# usb_io_v3_sch.net
KiCad netlist of a schematic drawn in Altium Designer
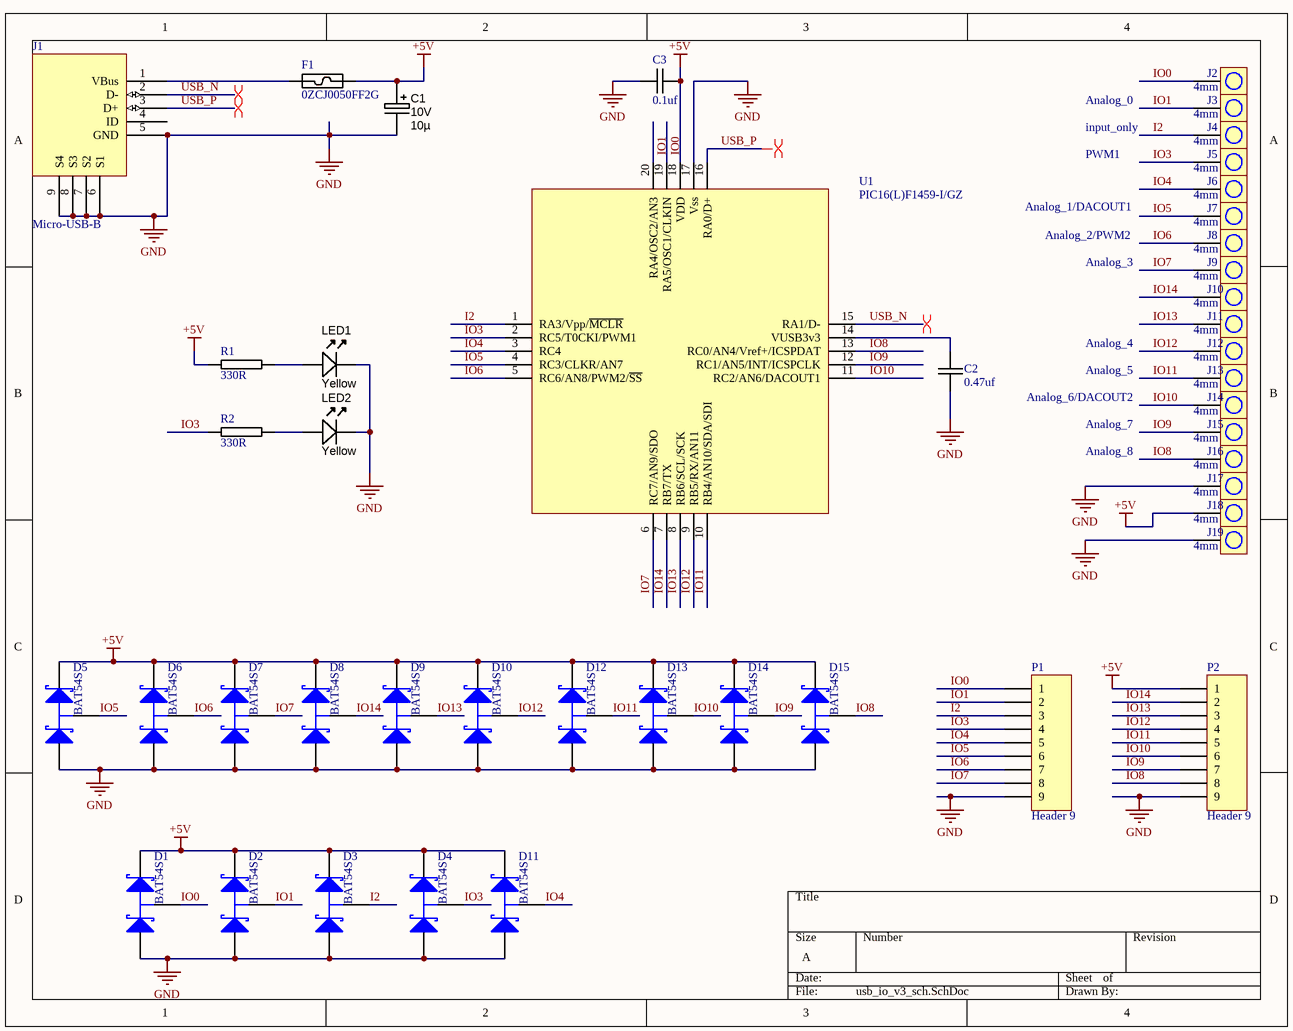
[diagram p0: usb_io_v3_sch.SchDoc]

(export (version "E")
  (design (tool "Eeschema 10.0.6"))
  (components
    (comp (ref "C1")
      (value "10µ")
      (footprint "CAPMP3528X210N")
      (description "Capacitor SMD Tantalum 47uF 20% 6.3V 1210")
      (fields (field (name "TOLERANCE") "±20%") (field (name "RATINGS") "10V"))
      (libsource (lib "PBL - Capacitors") (part "CAPT_47u_1210_6V3"))
    )
    (comp (ref "C2")
      (value "0.47uf")
      (footprint "0603C-GENERIC")
      (description "CAPACITOR 0603 CERAMIC")
      (fields
        (field (name "MANUFACTURER") "Murata Electronics North America")
        (field (name "MANUFACTURER PART NUMBER") "GRM188R60J106ME47D")
      )
      (libsource (lib "Generic") (part "0603C-10UF-6V3-X5R-MUR"))
    )
    (comp (ref "C3")
      (value "0.1uf")
      (footprint "0603C-GENERIC")
      (description "CAPACITOR 0603 CERAMIC")
      (fields
        (field (name "MANUFACTURER") "Murata Electronics North America")
        (field (name "MANUFACTURER PART NUMBER") "GRM188R60J106ME47D")
      )
      (libsource (lib "Generic") (part "0603C-10UF-6V3-X5R-MUR"))
    )
    (comp (ref "D1")
      (value "BAT54S")
      (footprint "SOT23_N")
      (description "Schottky Barrier Double Diode")
      (fields (field (name "PUBLISHER") "Altium Limited"))
      (libsource (lib "Philips Discrete Diode - Schottky") (part "BAT54S"))
    )
    (comp (ref "D2")
      (value "BAT54S")
      (footprint "SOT23_N")
      (description "Schottky Barrier Double Diode")
      (fields (field (name "PUBLISHER") "Altium Limited"))
      (libsource (lib "Philips Discrete Diode - Schottky") (part "BAT54S"))
    )
    (comp (ref "D3")
      (value "BAT54S")
      (footprint "SOT23_N")
      (description "Schottky Barrier Double Diode")
      (fields (field (name "PUBLISHER") "Altium Limited"))
      (libsource (lib "Philips Discrete Diode - Schottky") (part "BAT54S"))
    )
    (comp (ref "D4")
      (value "BAT54S")
      (footprint "SOT23_N")
      (description "Schottky Barrier Double Diode")
      (fields (field (name "PUBLISHER") "Altium Limited"))
      (libsource (lib "Philips Discrete Diode - Schottky") (part "BAT54S"))
    )
    (comp (ref "D5")
      (value "BAT54S")
      (footprint "SOT23_N")
      (description "Schottky Barrier Double Diode")
      (fields (field (name "PUBLISHER") "Altium Limited"))
      (libsource (lib "Philips Discrete Diode - Schottky") (part "BAT54S"))
    )
    (comp (ref "D6")
      (value "BAT54S")
      (footprint "SOT23_N")
      (description "Schottky Barrier Double Diode")
      (fields (field (name "PUBLISHER") "Altium Limited"))
      (libsource (lib "Philips Discrete Diode - Schottky") (part "BAT54S"))
    )
    (comp (ref "D7")
      (value "BAT54S")
      (footprint "SOT23_N")
      (description "Schottky Barrier Double Diode")
      (fields (field (name "PUBLISHER") "Altium Limited"))
      (libsource (lib "Philips Discrete Diode - Schottky") (part "BAT54S"))
    )
    (comp (ref "D8")
      (value "BAT54S")
      (footprint "SOT23_N")
      (description "Schottky Barrier Double Diode")
      (fields (field (name "PUBLISHER") "Altium Limited"))
      (libsource (lib "Philips Discrete Diode - Schottky") (part "BAT54S"))
    )
    (comp (ref "D9")
      (value "BAT54S")
      (footprint "SOT23_N")
      (description "Schottky Barrier Double Diode")
      (fields (field (name "PUBLISHER") "Altium Limited"))
      (libsource (lib "Philips Discrete Diode - Schottky") (part "BAT54S"))
    )
    (comp (ref "D10")
      (value "BAT54S")
      (footprint "SOT23_N")
      (description "Schottky Barrier Double Diode")
      (fields (field (name "PUBLISHER") "Altium Limited"))
      (libsource (lib "Philips Discrete Diode - Schottky") (part "BAT54S"))
    )
    (comp (ref "D11")
      (value "BAT54S")
      (footprint "SOT23_N")
      (description "Schottky Barrier Double Diode")
      (fields (field (name "PUBLISHER") "Altium Limited"))
      (libsource (lib "Philips Discrete Diode - Schottky") (part "BAT54S"))
    )
    (comp (ref "D12")
      (value "BAT54S")
      (footprint "SOT23_N")
      (description "Schottky Barrier Double Diode")
      (fields (field (name "PUBLISHER") "Altium Limited"))
      (libsource (lib "Philips Discrete Diode - Schottky") (part "BAT54S"))
    )
    (comp (ref "D13")
      (value "BAT54S")
      (footprint "SOT23_N")
      (description "Schottky Barrier Double Diode")
      (fields (field (name "PUBLISHER") "Altium Limited"))
      (libsource (lib "Philips Discrete Diode - Schottky") (part "BAT54S"))
    )
    (comp (ref "D14")
      (value "BAT54S")
      (footprint "SOT23_N")
      (description "Schottky Barrier Double Diode")
      (fields (field (name "PUBLISHER") "Altium Limited"))
      (libsource (lib "Philips Discrete Diode - Schottky") (part "BAT54S"))
    )
    (comp (ref "D15")
      (value "BAT54S")
      (footprint "SOT23_N")
      (description "Schottky Barrier Double Diode")
      (fields (field (name "PUBLISHER") "Altium Limited"))
      (libsource (lib "Philips Discrete Diode - Schottky") (part "BAT54S"))
    )
    (comp (ref "F1")
      (value "0ZCJ0050FF2G")
      (footprint "RESC3216N")
      (description "GENERIC FUSE")
      (libsource (lib "Generic") (part "FUSE-GENERIC"))
    )
    (comp (ref "J1")
      (value "Micro-USB-B")
      (footprint "10118193-0001lfc")
      (libsource (lib "USB-MICROB-HW-MC-5F") (part "Micro-USB-B"))
    )
    (comp (ref "J2")
      (value "4mm")
      (footprint "header_4mm_drill")
      (libsource (lib "headers") (part "Banana_4mm"))
    )
    (comp (ref "J3")
      (value "4mm")
      (footprint "header_4mm_drill")
      (libsource (lib "headers") (part "Banana_4mm"))
    )
    (comp (ref "J4")
      (value "4mm")
      (footprint "header_4mm_drill")
      (libsource (lib "headers") (part "Banana_4mm"))
    )
    (comp (ref "J5")
      (value "4mm")
      (footprint "header_4mm_drill")
      (libsource (lib "headers") (part "Banana_4mm"))
    )
    (comp (ref "J6")
      (value "4mm")
      (footprint "header_4mm_drill")
      (libsource (lib "headers") (part "Banana_4mm"))
    )
    (comp (ref "J7")
      (value "4mm")
      (footprint "header_4mm_drill")
      (libsource (lib "headers") (part "Banana_4mm"))
    )
    (comp (ref "J8")
      (value "4mm")
      (footprint "header_4mm_drill")
      (libsource (lib "headers") (part "Banana_4mm"))
    )
    (comp (ref "J9")
      (value "4mm")
      (footprint "header_4mm_drill")
      (libsource (lib "headers") (part "Banana_4mm"))
    )
    (comp (ref "J10")
      (value "4mm")
      (footprint "header_4mm_drill")
      (libsource (lib "headers") (part "Banana_4mm"))
    )
    (comp (ref "J11")
      (value "4mm")
      (footprint "header_4mm_drill")
      (libsource (lib "headers") (part "Banana_4mm"))
    )
    (comp (ref "J12")
      (value "4mm")
      (footprint "header_4mm_drill")
      (libsource (lib "headers") (part "Banana_4mm"))
    )
    (comp (ref "J13")
      (value "4mm")
      (footprint "header_4mm_drill")
      (libsource (lib "headers") (part "Banana_4mm"))
    )
    (comp (ref "J14")
      (value "4mm")
      (footprint "header_4mm_drill")
      (libsource (lib "headers") (part "Banana_4mm"))
    )
    (comp (ref "J15")
      (value "4mm")
      (footprint "header_4mm_drill")
      (libsource (lib "headers") (part "Banana_4mm"))
    )
    (comp (ref "J16")
      (value "4mm")
      (footprint "header_4mm_drill")
      (libsource (lib "headers") (part "Banana_4mm"))
    )
    (comp (ref "J17")
      (value "4mm")
      (footprint "header_4mm_drill")
      (libsource (lib "headers") (part "Banana_4mm"))
    )
    (comp (ref "J18")
      (value "4mm")
      (footprint "header_4mm_drill")
      (libsource (lib "headers") (part "Banana_4mm"))
    )
    (comp (ref "J19")
      (value "4mm")
      (footprint "header_4mm_drill")
      (libsource (lib "headers") (part "Banana_4mm"))
    )
    (comp (ref "LED1")
      (value "Yellow")
      (footprint "LED-0603-YELLOW")
      (description "LED 0603 SMD Yellow 590nm 150mcd 20mA")
      (libsource (lib "PBL - Light Sources") (part "LED_SMD_Yellow_0603_150mcd"))
    )
    (comp (ref "LED2")
      (value "Yellow")
      (footprint "LED-0603-YELLOW")
      (description "LED 0603 SMD Yellow 590nm 150mcd 20mA")
      (libsource (lib "PBL - Light Sources") (part "LED_SMD_Yellow_0603_150mcd"))
    )
    (comp (ref "P1")
      (value "Header 9")
      (footprint "HDR1X9")
      (description "Header, 9-Pin")
      (fields (field (name "PUBLISHER") "Altium Limited"))
      (libsource (lib "Miscellaneous Connectors") (part "Header 9"))
    )
    (comp (ref "P2")
      (value "Header 9")
      (footprint "HDR1X9")
      (description "Header, 9-Pin")
      (fields (field (name "PUBLISHER") "Altium Limited"))
      (libsource (lib "Miscellaneous Connectors") (part "Header 9"))
    )
    (comp (ref "R1")
      (value "330R")
      (footprint "0603R-2K2")
      (description "GENERIC RESISTOR 0603")
      (fields
        (field (name "MANUFACTURER PART NUMBER") "RMC 1/16 2.2K 1% R")
        (field (name "MANUFACTURER") "Stackpole Electronics Inc")
      )
      (libsource (lib "Generic") (part "0603R-2K2"))
    )
    (comp (ref "R2")
      (value "330R")
      (footprint "0603R-2K2")
      (description "GENERIC RESISTOR 0603")
      (fields
        (field (name "MANUFACTURER PART NUMBER") "RMC 1/16 2.2K 1% R")
        (field (name "MANUFACTURER") "Stackpole Electronics Inc")
      )
      (libsource (lib "Generic") (part "0603R-2K2"))
    )
    (comp (ref "U1")
      (value "PIC16(L)F1459-I/GZ")
      (footprint "UQFN20_4x4")
      (libsource (lib "microchip_my") (part "PIC16(L)F1459-I/GZ"))
    )
  )
  (nets
    (net (code "1") (name "+5V") (class "Default")
      (node (ref "C1") (pin "1") (pintype "passive"))
      (node (ref "C3") (pin "2") (pintype "passive"))
      (node (ref "D1") (pin "2") (pinfunction "K_2") (pintype "passive"))
      (node (ref "D10") (pin "2") (pinfunction "K_2") (pintype "passive"))
      (node (ref "D11") (pin "2") (pinfunction "K_2") (pintype "passive"))
      (node (ref "D12") (pin "2") (pinfunction "K_2") (pintype "passive"))
      (node (ref "D13") (pin "2") (pinfunction "K_2") (pintype "passive"))
      (node (ref "D14") (pin "2") (pinfunction "K_2") (pintype "passive"))
      (node (ref "D15") (pin "2") (pinfunction "K_2") (pintype "passive"))
      (node (ref "D2") (pin "2") (pinfunction "K_2") (pintype "passive"))
      (node (ref "D3") (pin "2") (pinfunction "K_2") (pintype "passive"))
      (node (ref "D4") (pin "2") (pinfunction "K_2") (pintype "passive"))
      (node (ref "D5") (pin "2") (pinfunction "K_2") (pintype "passive"))
      (node (ref "D6") (pin "2") (pinfunction "K_2") (pintype "passive"))
      (node (ref "D7") (pin "2") (pinfunction "K_2") (pintype "passive"))
      (node (ref "D8") (pin "2") (pinfunction "K_2") (pintype "passive"))
      (node (ref "D9") (pin "2") (pinfunction "K_2") (pintype "passive"))
      (node (ref "F1") (pin "2") (pintype "passive"))
      (node (ref "J18") (pin "1") (pinfunction "1_1") (pintype "passive"))
      (node (ref "P2") (pin "1") (pinfunction "1_1") (pintype "passive"))
      (node (ref "R1") (pin "2") (pintype "passive"))
      (node (ref "U1") (pin "18") (pinfunction "VDD_18") (pintype "power_in"))
    )
    (net (code "2") (name "/I2") (class "Default")
      (node (ref "D3") (pin "3") (pinfunction "C_3") (pintype "passive"))
      (node (ref "J4") (pin "1") (pinfunction "1_1") (pintype "passive"))
      (node (ref "P1") (pin "3") (pinfunction "3_3") (pintype "passive"))
      (node (ref "U1") (pin "1") (pinfunction "RA3/Vpp/~{MCLR}_1") (pintype "passive"))
    )
    (net (code "3") (name "/IO0") (class "Default")
      (node (ref "D1") (pin "3") (pinfunction "C_3") (pintype "passive"))
      (node (ref "J2") (pin "1") (pinfunction "1_1") (pintype "passive"))
      (node (ref "P1") (pin "1") (pinfunction "1_1") (pintype "passive"))
      (node (ref "U1") (pin "19") (pinfunction "RA5/OSC1/CLKIN_19") (pintype "passive"))
    )
    (net (code "4") (name "/IO1") (class "Default")
      (node (ref "D2") (pin "3") (pinfunction "C_3") (pintype "passive"))
      (node (ref "J3") (pin "1") (pinfunction "1_1") (pintype "passive"))
      (node (ref "P1") (pin "2") (pinfunction "2_2") (pintype "passive"))
      (node (ref "U1") (pin "20") (pinfunction "RA4/OSC2/AN3_20") (pintype "passive"))
    )
    (net (code "5") (name "/IO3") (class "Default")
      (node (ref "D4") (pin "3") (pinfunction "C_3") (pintype "passive"))
      (node (ref "J5") (pin "1") (pinfunction "1_1") (pintype "passive"))
      (node (ref "P1") (pin "4") (pinfunction "4_4") (pintype "passive"))
      (node (ref "R2") (pin "2") (pintype "passive"))
      (node (ref "U1") (pin "2") (pinfunction "RC5/T0CKI/PWM1_2") (pintype "passive"))
    )
    (net (code "6") (name "/IO4") (class "Default")
      (node (ref "D11") (pin "3") (pinfunction "C_3") (pintype "passive"))
      (node (ref "J6") (pin "1") (pinfunction "1_1") (pintype "passive"))
      (node (ref "P1") (pin "5") (pinfunction "5_5") (pintype "passive"))
      (node (ref "U1") (pin "3") (pinfunction "RC4_3") (pintype "passive"))
    )
    (net (code "7") (name "/IO5") (class "Default")
      (node (ref "D5") (pin "3") (pinfunction "C_3") (pintype "passive"))
      (node (ref "J7") (pin "1") (pinfunction "1_1") (pintype "passive"))
      (node (ref "P1") (pin "6") (pinfunction "6_6") (pintype "passive"))
      (node (ref "U1") (pin "4") (pinfunction "RC3/CLKR/AN7_4") (pintype "passive"))
    )
    (net (code "8") (name "/IO6") (class "Default")
      (node (ref "D6") (pin "3") (pinfunction "C_3") (pintype "passive"))
      (node (ref "J8") (pin "1") (pinfunction "1_1") (pintype "passive"))
      (node (ref "P1") (pin "7") (pinfunction "7_7") (pintype "passive"))
      (node (ref "U1") (pin "5") (pinfunction "RC6/AN8/PWM2/~{SS}_5") (pintype "passive"))
    )
    (net (code "9") (name "/IO7") (class "Default")
      (node (ref "D7") (pin "3") (pinfunction "C_3") (pintype "passive"))
      (node (ref "J9") (pin "1") (pinfunction "1_1") (pintype "passive"))
      (node (ref "P1") (pin "8") (pinfunction "8_8") (pintype "passive"))
      (node (ref "U1") (pin "6") (pinfunction "RC7/AN9/SDO_6") (pintype "passive"))
    )
    (net (code "10") (name "/IO8") (class "Default")
      (node (ref "D15") (pin "3") (pinfunction "C_3") (pintype "passive"))
      (node (ref "J16") (pin "1") (pinfunction "1_1") (pintype "passive"))
      (node (ref "P2") (pin "8") (pinfunction "8_8") (pintype "passive"))
      (node (ref "U1") (pin "13") (pinfunction "RC0/AN4/Vref+/ICSPDAT_13") (pintype "passive"))
    )
    (net (code "11") (name "/IO9") (class "Default")
      (node (ref "D14") (pin "3") (pinfunction "C_3") (pintype "passive"))
      (node (ref "J15") (pin "1") (pinfunction "1_1") (pintype "passive"))
      (node (ref "P2") (pin "7") (pinfunction "7_7") (pintype "passive"))
      (node (ref "U1") (pin "12") (pinfunction "RC1/AN5/INT/ICSPCLK_12") (pintype "passive"))
    )
    (net (code "12") (name "/IO10") (class "Default")
      (node (ref "D13") (pin "3") (pinfunction "C_3") (pintype "passive"))
      (node (ref "J14") (pin "1") (pinfunction "1_1") (pintype "passive"))
      (node (ref "P2") (pin "6") (pinfunction "6_6") (pintype "passive"))
      (node (ref "U1") (pin "11") (pinfunction "RC2/AN6/DACOUT1_11") (pintype "passive"))
    )
    (net (code "13") (name "/IO11") (class "Default")
      (node (ref "D12") (pin "3") (pinfunction "C_3") (pintype "passive"))
      (node (ref "J13") (pin "1") (pinfunction "1_1") (pintype "passive"))
      (node (ref "P2") (pin "5") (pinfunction "5_5") (pintype "passive"))
      (node (ref "U1") (pin "10") (pinfunction "RB4/AN10/SDA/SDI_10") (pintype "passive"))
    )
    (net (code "14") (name "/IO12") (class "Default")
      (node (ref "D10") (pin "3") (pinfunction "C_3") (pintype "passive"))
      (node (ref "J12") (pin "1") (pinfunction "1_1") (pintype "passive"))
      (node (ref "P2") (pin "4") (pinfunction "4_4") (pintype "passive"))
      (node (ref "U1") (pin "9") (pinfunction "RB5/RX/AN11_9") (pintype "passive"))
    )
    (net (code "15") (name "/IO13") (class "Default")
      (node (ref "D9") (pin "3") (pinfunction "C_3") (pintype "passive"))
      (node (ref "J11") (pin "1") (pinfunction "1_1") (pintype "passive"))
      (node (ref "P2") (pin "3") (pinfunction "3_3") (pintype "passive"))
      (node (ref "U1") (pin "8") (pinfunction "RB6/SCL/SCK_8") (pintype "passive"))
    )
    (net (code "16") (name "/IO14") (class "Default")
      (node (ref "D8") (pin "3") (pinfunction "C_3") (pintype "passive"))
      (node (ref "J10") (pin "1") (pinfunction "1_1") (pintype "passive"))
      (node (ref "P2") (pin "2") (pinfunction "2_2") (pintype "passive"))
      (node (ref "U1") (pin "7") (pinfunction "RB7/TX_7") (pintype "passive"))
    )
    (net (code "17") (name "/USB_N") (class "Default")
      (node (ref "J1") (pin "2") (pinfunction "D-_2") (pintype "bidirectional"))
      (node (ref "U1") (pin "15") (pinfunction "RA1/D-_15") (pintype "passive"))
    )
    (net (code "18") (name "/USB_P") (class "Default")
      (node (ref "J1") (pin "3") (pinfunction "D+_3") (pintype "bidirectional"))
      (node (ref "U1") (pin "16") (pinfunction "RA0/D+_16") (pintype "passive"))
    )
    (net (code "19") (name "GND") (class "Default")
      (node (ref "C1") (pin "2") (pintype "passive"))
      (node (ref "C2") (pin "1") (pintype "passive"))
      (node (ref "C3") (pin "1") (pintype "passive"))
      (node (ref "D1") (pin "1") (pinfunction "A_1") (pintype "passive"))
      (node (ref "D10") (pin "1") (pinfunction "A_1") (pintype "passive"))
      (node (ref "D11") (pin "1") (pinfunction "A_1") (pintype "passive"))
      (node (ref "D12") (pin "1") (pinfunction "A_1") (pintype "passive"))
      (node (ref "D13") (pin "1") (pinfunction "A_1") (pintype "passive"))
      (node (ref "D14") (pin "1") (pinfunction "A_1") (pintype "passive"))
      (node (ref "D15") (pin "1") (pinfunction "A_1") (pintype "passive"))
      (node (ref "D2") (pin "1") (pinfunction "A_1") (pintype "passive"))
      (node (ref "D3") (pin "1") (pinfunction "A_1") (pintype "passive"))
      (node (ref "D4") (pin "1") (pinfunction "A_1") (pintype "passive"))
      (node (ref "D5") (pin "1") (pinfunction "A_1") (pintype "passive"))
      (node (ref "D6") (pin "1") (pinfunction "A_1") (pintype "passive"))
      (node (ref "D7") (pin "1") (pinfunction "A_1") (pintype "passive"))
      (node (ref "D8") (pin "1") (pinfunction "A_1") (pintype "passive"))
      (node (ref "D9") (pin "1") (pinfunction "A_1") (pintype "passive"))
      (node (ref "J1") (pin "5") (pinfunction "GND_5") (pintype "power_in"))
      (node (ref "J1") (pin "6") (pinfunction "S1_6") (pintype "passive"))
      (node (ref "J1") (pin "7") (pinfunction "S2_7") (pintype "power_in"))
      (node (ref "J1") (pin "8") (pinfunction "S3_8") (pintype "power_in"))
      (node (ref "J1") (pin "9") (pinfunction "S4_9") (pintype "power_in"))
      (node (ref "J17") (pin "1") (pinfunction "1_1") (pintype "passive"))
      (node (ref "J19") (pin "1") (pinfunction "1_1") (pintype "passive"))
      (node (ref "LED1") (pin "K") (pinfunction "K_K") (pintype "passive"))
      (node (ref "LED2") (pin "K") (pinfunction "K_K") (pintype "passive"))
      (node (ref "P1") (pin "9") (pinfunction "9_9") (pintype "passive"))
      (node (ref "P2") (pin "9") (pinfunction "9_9") (pintype "passive"))
      (node (ref "U1") (pin "17") (pinfunction "Vss_17") (pintype "passive"))
    )
    (net (code "20") (name "Net-(J1-VBus)") (class "Default")
      (node (ref "F1") (pin "1") (pintype "passive"))
      (node (ref "J1") (pin "1") (pinfunction "VBus_1") (pintype "power_in"))
    )
    (net (code "21") (name "Net-(LED1-PadA)") (class "Default")
      (node (ref "LED1") (pin "A") (pinfunction "A_A") (pintype "passive"))
      (node (ref "R1") (pin "1") (pintype "passive"))
    )
    (net (code "22") (name "Net-(LED2-PadA)") (class "Default")
      (node (ref "LED2") (pin "A") (pinfunction "A_A") (pintype "passive"))
      (node (ref "R2") (pin "1") (pintype "passive"))
    )
    (net (code "23") (name "Net-(U1-VUSB3v3)") (class "Default")
      (node (ref "C2") (pin "2") (pintype "passive"))
      (node (ref "U1") (pin "14") (pinfunction "VUSB3v3_14") (pintype "passive"))
    )
    (net (code "24") (name "unconnected-(J1-ID-Pad4)") (class "Default")
      (node (ref "J1") (pin "4") (pinfunction "ID_4") (pintype "passive"))
    )
  )
)
